# Burglar_alarm.net
KiCad netlist of a schematic drawn in EAGLE
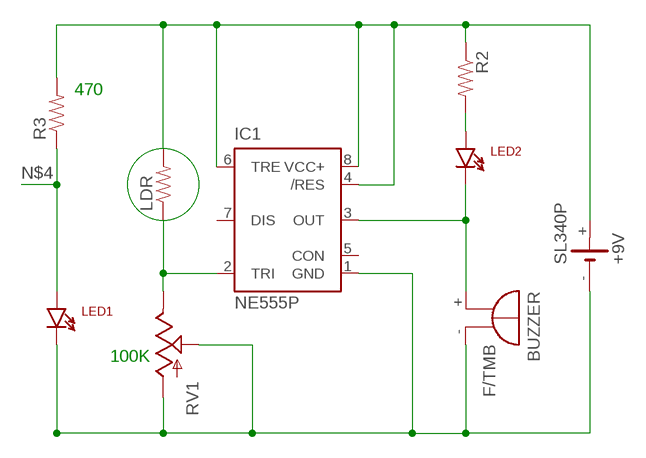
[diagram p0: schematic, sheet 1]

(export (version "E")
  (design (tool "Eeschema 10.0.6"))
  (components
    (comp (ref "+9V")
      (value "SL340P")
      (footprint "eagle-import:SL-340_P3.6V")
      (libsource (lib "eagle-import") (part "SL340P"))
    )
    (comp (ref "BUZZER")
      (value "F/TMB")
      (footprint "eagle-import:F_TMB")
      (libsource (lib "eagle-import") (part "F/TMB"))
    )
    (comp (ref "IC1")
      (value "NE555P")
      (footprint "eagle-import:DIL-08")
      (fields (field (name "MF") "Arrow Electronics") (field (name "MPN") "NE555N"))
      (libsource (lib "eagle-import") (part "NE555P"))
    )
    (comp (ref "LDR")
      (value "RESISTORAXIAL-0.3")
      (footprint "eagle-import:AXIAL-0.3")
      (libsource (lib "eagle-import") (part "RESISTORAXIAL-0.3"))
    )
    (comp (ref "LED1")
      (value "LTE-302")
      (footprint "eagle-import:LTE-302")
      (libsource (lib "eagle-import") (part "LTE-302"))
    )
    (comp (ref "LED2")
      (value "LTE-302")
      (footprint "eagle-import:LTE-302")
      (libsource (lib "eagle-import") (part "LTE-302"))
    )
    (comp (ref "R2")
      (value "RESISTORAXIAL-0.3")
      (footprint "eagle-import:AXIAL-0.3")
      (libsource (lib "eagle-import") (part "RESISTORAXIAL-0.3"))
    )
    (comp (ref "R3")
      (value "RESISTORAXIAL-0.3")
      (footprint "eagle-import:AXIAL-0.3")
      (libsource (lib "eagle-import") (part "RESISTORAXIAL-0.3"))
    )
    (comp (ref "RV1")
      (value "POTTRIM")
      (footprint "eagle-import:TRIM_POT")
      (libsource (lib "eagle-import") (part "POTTRIM"))
    )
  )
  (nets
    (net (code "1") (name "/N$4") (class "Default")
      (node (ref "LED1") (pin "A") (pinfunction "A_A") (pintype "bidirectional"))
      (node (ref "R3") (pin "P$1") (pinfunction "1_P$1") (pintype "passive"))
    )
    (net (code "2") (name "Net-(IC1-GND)") (class "Default")
      (node (ref "+9V") (pin "-") (pinfunction "-_-") (pintype "passive"))
      (node (ref "BUZZER") (pin "-") (pinfunction "-_-") (pintype "passive"))
      (node (ref "IC1") (pin "1") (pinfunction "GND_1") (pintype "power_in"))
      (node (ref "LED1") (pin "C") (pinfunction "C_C") (pintype "bidirectional"))
      (node (ref "RV1") (pin "1") (pinfunction "S_1") (pintype "passive"))
      (node (ref "RV1") (pin "3") (pinfunction "A_3") (pintype "passive"))
    )
    (net (code "3") (name "Net-(IC1-OUT)") (class "Default")
      (node (ref "BUZZER") (pin "+") (pinfunction "+_+") (pintype "passive"))
      (node (ref "IC1") (pin "3") (pinfunction "OUT_3") (pintype "output"))
      (node (ref "LED2") (pin "C") (pinfunction "C_C") (pintype "bidirectional"))
    )
    (net (code "4") (name "Net-(IC1-TRE)") (class "Default")
      (node (ref "+9V") (pin "+") (pinfunction "+_+") (pintype "passive"))
      (node (ref "IC1") (pin "4") (pinfunction "/RES_4") (pintype "input"))
      (node (ref "IC1") (pin "6") (pinfunction "TRE_6") (pintype "input"))
      (node (ref "IC1") (pin "8") (pinfunction "VCC+_8") (pintype "power_in"))
      (node (ref "LDR") (pin "P$2") (pinfunction "2_P$2") (pintype "passive"))
      (node (ref "R2") (pin "P$1") (pinfunction "1_P$1") (pintype "passive"))
      (node (ref "R3") (pin "P$2") (pinfunction "2_P$2") (pintype "passive"))
    )
    (net (code "5") (name "Net-(IC1-TRI)") (class "Default")
      (node (ref "IC1") (pin "2") (pinfunction "TRI_2") (pintype "input"))
      (node (ref "LDR") (pin "P$1") (pinfunction "1_P$1") (pintype "passive"))
      (node (ref "RV1") (pin "2") (pinfunction "E_2") (pintype "passive"))
    )
    (net (code "6") (name "Net-(R2-2)") (class "Default")
      (node (ref "LED2") (pin "A") (pinfunction "A_A") (pintype "bidirectional"))
      (node (ref "R2") (pin "P$2") (pinfunction "2_P$2") (pintype "passive"))
    )
    (net (code "7") (name "unconnected-(IC1-CON-Pad5)") (class "Default")
      (node (ref "IC1") (pin "5") (pinfunction "CON_5") (pintype "input"))
    )
    (net (code "8") (name "unconnected-(IC1-DIS-Pad7)") (class "Default")
      (node (ref "IC1") (pin "7") (pinfunction "DIS_7") (pintype "input"))
    )
  )
)
